# 2364_ROM-el_v1.net
KiCad netlist of a schematic drawn in EAGLE
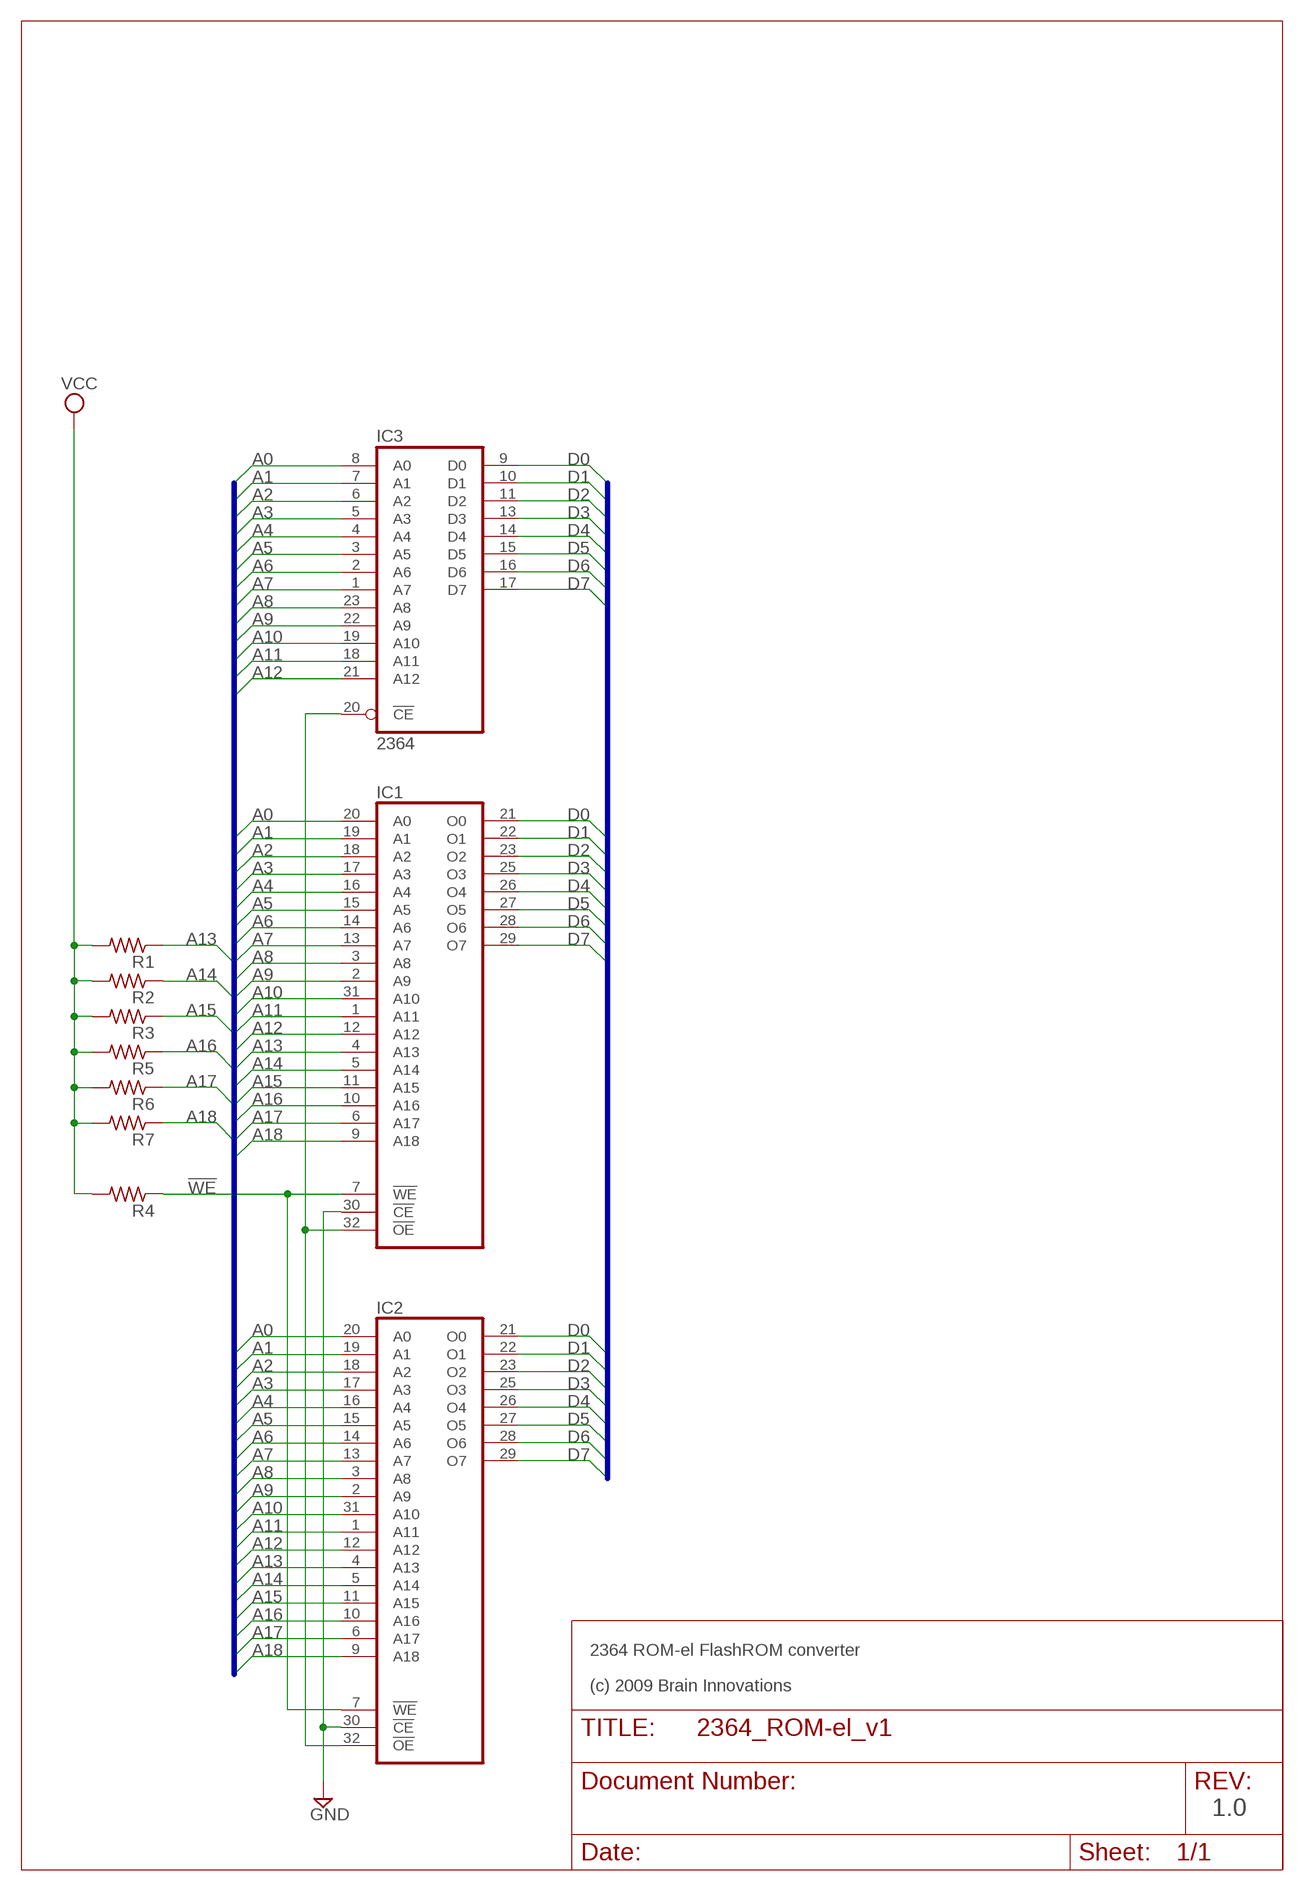
[diagram p0: schematic, sheet 1]

(export (version "E")
  (design (tool "Eeschema 10.0.6"))
  (components
    (comp (ref "IC1")
      (value "FLASH_RAM4096KB'T'")
      (footprint "eagle-import:TSOP32")
      (libsource (lib "eagle-import") (part "FLASH_RAM4096KB'T'"))
    )
    (comp (ref "IC2")
      (value "FLASH_RAM4096KB'V'")
      (footprint "eagle-import:VSOP32")
      (libsource (lib "eagle-import") (part "FLASH_RAM4096KB'V'"))
    )
    (comp (ref "IC3")
      (value "2364")
      (footprint "eagle-import:DIL24-ROUNDPAD")
      (libsource (lib "eagle-import") (part "2364-RP"))
    )
    (comp (ref "R1")
      (value "R-US_R0805")
      (footprint "eagle-import:R0805")
      (libsource (lib "eagle-import") (part "R-US_R0805"))
    )
    (comp (ref "R2")
      (value "R-US_R0805")
      (footprint "eagle-import:R0805")
      (libsource (lib "eagle-import") (part "R-US_R0805"))
    )
    (comp (ref "R3")
      (value "R-US_R0805")
      (footprint "eagle-import:R0805")
      (libsource (lib "eagle-import") (part "R-US_R0805"))
    )
    (comp (ref "R4")
      (value "R-US_R0805")
      (footprint "eagle-import:R0805")
      (libsource (lib "eagle-import") (part "R-US_R0805"))
    )
    (comp (ref "R5")
      (value "R-US_R0805")
      (footprint "eagle-import:R0805")
      (libsource (lib "eagle-import") (part "R-US_R0805"))
    )
    (comp (ref "R6")
      (value "R-US_R0805")
      (footprint "eagle-import:R0805")
      (libsource (lib "eagle-import") (part "R-US_R0805"))
    )
    (comp (ref "R7")
      (value "R-US_R0805")
      (footprint "eagle-import:R0805")
      (libsource (lib "eagle-import") (part "R-US_R0805"))
    )
  )
  (nets
    (net (code "1") (name "/A0") (class "Default")
      (node (ref "IC1") (pin "20") (pinfunction "A0_20") (pintype "input"))
      (node (ref "IC2") (pin "20") (pinfunction "A0_20") (pintype "input"))
      (node (ref "IC3") (pin "8") (pinfunction "A0_8") (pintype "bidirectional"))
    )
    (net (code "2") (name "/A1") (class "Default")
      (node (ref "IC1") (pin "19") (pinfunction "A1_19") (pintype "input"))
      (node (ref "IC2") (pin "19") (pinfunction "A1_19") (pintype "input"))
      (node (ref "IC3") (pin "7") (pinfunction "A1_7") (pintype "bidirectional"))
    )
    (net (code "3") (name "/A2") (class "Default")
      (node (ref "IC1") (pin "18") (pinfunction "A2_18") (pintype "input"))
      (node (ref "IC2") (pin "18") (pinfunction "A2_18") (pintype "input"))
      (node (ref "IC3") (pin "6") (pinfunction "A2_6") (pintype "bidirectional"))
    )
    (net (code "4") (name "/A3") (class "Default")
      (node (ref "IC1") (pin "17") (pinfunction "A3_17") (pintype "input"))
      (node (ref "IC2") (pin "17") (pinfunction "A3_17") (pintype "input"))
      (node (ref "IC3") (pin "5") (pinfunction "A3_5") (pintype "bidirectional"))
    )
    (net (code "5") (name "/A4") (class "Default")
      (node (ref "IC1") (pin "16") (pinfunction "A4_16") (pintype "input"))
      (node (ref "IC2") (pin "16") (pinfunction "A4_16") (pintype "input"))
      (node (ref "IC3") (pin "4") (pinfunction "A4_4") (pintype "bidirectional"))
    )
    (net (code "6") (name "/A5") (class "Default")
      (node (ref "IC1") (pin "15") (pinfunction "A5_15") (pintype "input"))
      (node (ref "IC2") (pin "15") (pinfunction "A5_15") (pintype "input"))
      (node (ref "IC3") (pin "3") (pinfunction "A5_3") (pintype "bidirectional"))
    )
    (net (code "7") (name "/A6") (class "Default")
      (node (ref "IC1") (pin "14") (pinfunction "A6_14") (pintype "input"))
      (node (ref "IC2") (pin "14") (pinfunction "A6_14") (pintype "input"))
      (node (ref "IC3") (pin "2") (pinfunction "A6_2") (pintype "bidirectional"))
    )
    (net (code "8") (name "/A7") (class "Default")
      (node (ref "IC1") (pin "13") (pinfunction "A7_13") (pintype "input"))
      (node (ref "IC2") (pin "13") (pinfunction "A7_13") (pintype "input"))
      (node (ref "IC3") (pin "1") (pinfunction "A7_1") (pintype "bidirectional"))
    )
    (net (code "9") (name "/A8") (class "Default")
      (node (ref "IC1") (pin "3") (pinfunction "A8_3") (pintype "input"))
      (node (ref "IC2") (pin "3") (pinfunction "A8_3") (pintype "input"))
      (node (ref "IC3") (pin "23") (pinfunction "A8_23") (pintype "bidirectional"))
    )
    (net (code "10") (name "/A9") (class "Default")
      (node (ref "IC1") (pin "2") (pinfunction "A9_2") (pintype "input"))
      (node (ref "IC2") (pin "2") (pinfunction "A9_2") (pintype "input"))
      (node (ref "IC3") (pin "22") (pinfunction "A9_22") (pintype "bidirectional"))
    )
    (net (code "11") (name "/A10") (class "Default")
      (node (ref "IC1") (pin "31") (pinfunction "A10_31") (pintype "input"))
      (node (ref "IC2") (pin "31") (pinfunction "A10_31") (pintype "input"))
      (node (ref "IC3") (pin "19") (pinfunction "A10_19") (pintype "bidirectional"))
    )
    (net (code "12") (name "/A11") (class "Default")
      (node (ref "IC1") (pin "1") (pinfunction "A11_1") (pintype "input"))
      (node (ref "IC2") (pin "1") (pinfunction "A11_1") (pintype "input"))
      (node (ref "IC3") (pin "18") (pinfunction "A11_18") (pintype "bidirectional"))
    )
    (net (code "13") (name "/A12") (class "Default")
      (node (ref "IC1") (pin "12") (pinfunction "A12_12") (pintype "input"))
      (node (ref "IC2") (pin "12") (pinfunction "A12_12") (pintype "input"))
      (node (ref "IC3") (pin "21") (pinfunction "A12_21") (pintype "bidirectional"))
    )
    (net (code "14") (name "/A13") (class "Default")
      (node (ref "IC1") (pin "4") (pinfunction "A13_4") (pintype "input"))
      (node (ref "IC2") (pin "4") (pinfunction "A13_4") (pintype "input"))
      (node (ref "R1") (pin "1") (pinfunction "1_1") (pintype "passive"))
    )
    (net (code "15") (name "/A14") (class "Default")
      (node (ref "IC1") (pin "5") (pinfunction "A14_5") (pintype "input"))
      (node (ref "IC2") (pin "5") (pinfunction "A14_5") (pintype "input"))
      (node (ref "R2") (pin "1") (pinfunction "1_1") (pintype "passive"))
    )
    (net (code "16") (name "/A15") (class "Default")
      (node (ref "IC1") (pin "11") (pinfunction "A15_11") (pintype "input"))
      (node (ref "IC2") (pin "11") (pinfunction "A15_11") (pintype "input"))
      (node (ref "R3") (pin "1") (pinfunction "1_1") (pintype "passive"))
    )
    (net (code "17") (name "/A16") (class "Default")
      (node (ref "IC1") (pin "10") (pinfunction "A16_10") (pintype "input"))
      (node (ref "IC2") (pin "10") (pinfunction "A16_10") (pintype "input"))
      (node (ref "R5") (pin "1") (pinfunction "1_1") (pintype "passive"))
    )
    (net (code "18") (name "/A17") (class "Default")
      (node (ref "IC1") (pin "6") (pinfunction "A17_6") (pintype "input"))
      (node (ref "IC2") (pin "6") (pinfunction "A17_6") (pintype "input"))
      (node (ref "R6") (pin "1") (pinfunction "1_1") (pintype "passive"))
    )
    (net (code "19") (name "/A18") (class "Default")
      (node (ref "IC1") (pin "9") (pinfunction "A18_9") (pintype "input"))
      (node (ref "IC2") (pin "9") (pinfunction "A18_9") (pintype "input"))
      (node (ref "R7") (pin "1") (pinfunction "1_1") (pintype "passive"))
    )
    (net (code "20") (name "/D0") (class "Default")
      (node (ref "IC1") (pin "21") (pinfunction "O0_21") (pintype "tri_state"))
      (node (ref "IC2") (pin "21") (pinfunction "O0_21") (pintype "tri_state"))
      (node (ref "IC3") (pin "9") (pinfunction "D0_9") (pintype "tri_state"))
    )
    (net (code "21") (name "/D1") (class "Default")
      (node (ref "IC1") (pin "22") (pinfunction "O1_22") (pintype "tri_state"))
      (node (ref "IC2") (pin "22") (pinfunction "O1_22") (pintype "tri_state"))
      (node (ref "IC3") (pin "10") (pinfunction "D1_10") (pintype "tri_state"))
    )
    (net (code "22") (name "/D2") (class "Default")
      (node (ref "IC1") (pin "23") (pinfunction "O2_23") (pintype "tri_state"))
      (node (ref "IC2") (pin "23") (pinfunction "O2_23") (pintype "tri_state"))
      (node (ref "IC3") (pin "11") (pinfunction "D2_11") (pintype "tri_state"))
    )
    (net (code "23") (name "/D3") (class "Default")
      (node (ref "IC1") (pin "25") (pinfunction "O3_25") (pintype "tri_state"))
      (node (ref "IC2") (pin "25") (pinfunction "O3_25") (pintype "tri_state"))
      (node (ref "IC3") (pin "13") (pinfunction "D3_13") (pintype "tri_state"))
    )
    (net (code "24") (name "/D4") (class "Default")
      (node (ref "IC1") (pin "26") (pinfunction "O4_26") (pintype "tri_state"))
      (node (ref "IC2") (pin "26") (pinfunction "O4_26") (pintype "tri_state"))
      (node (ref "IC3") (pin "14") (pinfunction "D4_14") (pintype "tri_state"))
    )
    (net (code "25") (name "/D5") (class "Default")
      (node (ref "IC1") (pin "27") (pinfunction "O5_27") (pintype "tri_state"))
      (node (ref "IC2") (pin "27") (pinfunction "O5_27") (pintype "tri_state"))
      (node (ref "IC3") (pin "15") (pinfunction "D5_15") (pintype "tri_state"))
    )
    (net (code "26") (name "/D6") (class "Default")
      (node (ref "IC1") (pin "28") (pinfunction "O6_28") (pintype "tri_state"))
      (node (ref "IC2") (pin "28") (pinfunction "O6_28") (pintype "tri_state"))
      (node (ref "IC3") (pin "16") (pinfunction "D6_16") (pintype "tri_state"))
    )
    (net (code "27") (name "/D7") (class "Default")
      (node (ref "IC1") (pin "29") (pinfunction "O7_29") (pintype "tri_state"))
      (node (ref "IC2") (pin "29") (pinfunction "O7_29") (pintype "tri_state"))
      (node (ref "IC3") (pin "17") (pinfunction "D7_17") (pintype "tri_state"))
    )
    (net (code "28") (name "/~{WE}") (class "Default")
      (node (ref "IC1") (pin "7") (pinfunction "~{WE}_7") (pintype "input"))
      (node (ref "IC2") (pin "7") (pinfunction "~{WE}_7") (pintype "input"))
      (node (ref "R4") (pin "1") (pinfunction "1_1") (pintype "passive"))
    )
    (net (code "29") (name "GND") (class "Default")
      (node (ref "IC1") (pin "30") (pinfunction "~{CE}_30") (pintype "input"))
      (node (ref "IC2") (pin "30") (pinfunction "~{CE}_30") (pintype "input"))
    )
    (net (code "30") (name "Net-(IC1A-~{OE})") (class "Default")
      (node (ref "IC1") (pin "32") (pinfunction "~{OE}_32") (pintype "input"))
      (node (ref "IC2") (pin "32") (pinfunction "~{OE}_32") (pintype "input"))
      (node (ref "IC3") (pin "20") (pinfunction "~{CE}_20") (pintype "input"))
    )
    (net (code "31") (name "VCC") (class "Default")
      (node (ref "R1") (pin "2") (pinfunction "2_2") (pintype "passive"))
      (node (ref "R2") (pin "2") (pinfunction "2_2") (pintype "passive"))
      (node (ref "R3") (pin "2") (pinfunction "2_2") (pintype "passive"))
      (node (ref "R4") (pin "2") (pinfunction "2_2") (pintype "passive"))
      (node (ref "R5") (pin "2") (pinfunction "2_2") (pintype "passive"))
      (node (ref "R6") (pin "2") (pinfunction "2_2") (pintype "passive"))
      (node (ref "R7") (pin "2") (pinfunction "2_2") (pintype "passive"))
    )
  )
)
